# VNH5019.net
KiCad netlist of a schematic drawn in Altium Designer
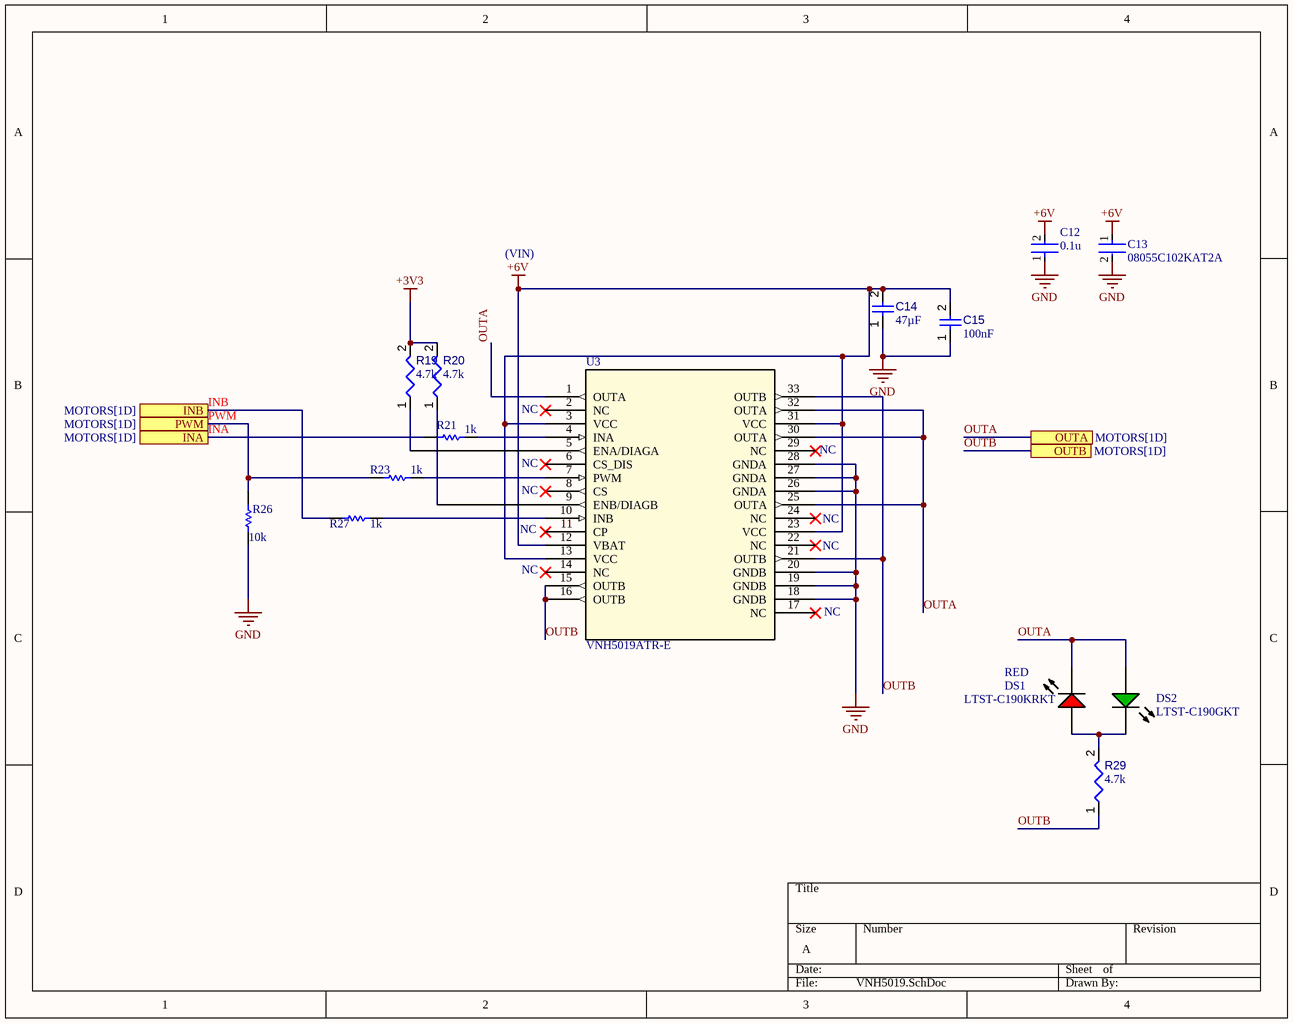
[diagram p0: VNH5019.SchDoc]

(export (version "E")
  (design (tool "Eeschema 10.0.6"))
  (components
    (comp (ref "C12")
      (value "0.1u")
      (footprint "FP-CL21-IPC_A")
      (description "CL21 Series 0805 100nF 100V ±10% Tolerance X7R Multilayer Ceramic Chip Capacitor")
      (libsource (lib "Altium Content Vault") (part "b4654b650e69147ec39a6b967a45e02"))
    )
    (comp (ref "C13")
      (value "08055C102KAT2A")
      (footprint "FP-0805-L_2_01_0_2-W_1_25-IPC_C")
      (description "General Purpose Ceramic Capacitor, 0805, 1nF, 10%, X7R, 0.15, 50V")
      (fields (field (name "VOLTAGE") "50V") (field (name "TOLERANCE") "10%"))
      (libsource (lib "Altium Content Vault") (part "02cd4be3c70576c341d710602a673aa"))
    )
    (comp (ref "C14")
      (value "47µF")
      (footprint "CAPC0805(2012)145_L")
      (description "Chip Capacitor, 47µF +/-40%, 6.3V, 0805, Thickness 1.45 mm")
      (fields (field (name "TOLERANCE") "10%") (field (name "Comment") "Capacitor 47µF +/-40% 6.3V 0805"))
      (libsource (lib "Northeastern University - Generate") (part "CAP-NP-2"))
    )
    (comp (ref "C15")
      (value "100nF")
      (footprint "CAPC2013X95X50LL10T25")
      (description "Chip Capacitor, 100 nF, +/- 10%, 50 V, 0805 (2012 Metric)")
      (fields (field (name "TOLERANCE") "10%") (field (name "Comment") "Capacitor 100 nF +/-10% 50 V 0805"))
      (libsource (lib "Northeastern University - Generate") (part "CAP-NP-2"))
    )
    (comp (ref "DS1")
      (value "LTST-C190KRKT")
      (footprint "LTST-C191KRKT_V")
      (description "LED Uni-Color Red, 62.5 mW, 25 mA, -30 to 85 degC, 2-Pin SMD, RoHS, Tape and Reel")
      (fields (field (name "POWER") "75mW") (field (name "MANUFACTURER") "Lite-On"))
      (libsource (lib "Northeastern University - Generate") (part "LED-RED-AK-2"))
    )
    (comp (ref "DS2")
      (value "LTST-C190GKT")
      (footprint "LTST-C190GKT_V")
      (description "LED Uni-Color Green, 100 mW, 30 mA, -55 to 85 degC, 2-Pin SMD, RoHS, Tape and Reel")
      (fields (field (name "POWER") "100mW") (field (name "MANUFACTURER") "Lite-On"))
      (libsource (lib "Northeastern University - Generate") (part "LED-GREEN-AK-2"))
    )
    (comp (ref "R19")
      (value "4.7k")
      (footprint "RESC2013X70X40ML20T20")
      (description "Chip Resistor, 4.7 KOhm, +/- 1%, 0.125 W, -55 to 155 degC, 0805 (2012 Metric)")
      (fields (field (name "POWER") "125mW") (field (name "TOLERANCE") "1%"))
      (libsource (lib "Northeastern University - Generate") (part "RES-2"))
    )
    (comp (ref "R20")
      (value "4.7k")
      (footprint "RESC2013X70X40ML20T20")
      (description "Chip Resistor, 4.7 KOhm, +/- 1%, 0.125 W, -55 to 155 degC, 0805 (2012 Metric)")
      (fields (field (name "POWER") "125mW") (field (name "TOLERANCE") "1%"))
      (libsource (lib "Northeastern University - Generate") (part "RES-2"))
    )
    (comp (ref "R21")
      (value "1k")
      (footprint "RESC2013X60X35ML10T20")
      (description "Chip Resistor, 1 KOhm, +/- 1%, 125 mW, -55 to 155 degC, 0805 (2012 Metric), RoHS, Tape and Reel")
      (fields (field (name "TOLERANCE") "1%") (field (name "MANUFACTURER") "Yageo"))
      (libsource (lib "Altium Content Vault") (part "RES-2"))
    )
    (comp (ref "R23")
      (value "1k")
      (footprint "RESC2013X60X35ML10T20")
      (description "Chip Resistor, 1 KOhm, +/- 1%, 125 mW, -55 to 155 degC, 0805 (2012 Metric), RoHS, Tape and Reel")
      (fields (field (name "TOLERANCE") "1%") (field (name "MANUFACTURER") "Yageo"))
      (libsource (lib "Altium Content Vault") (part "RES-2"))
    )
    (comp (ref "R26")
      (value "10k")
      (footprint "RESC2013X60X40LL20T25_A")
      (fields (field (name "TOLERANCE") "0.1%") (field (name "MANUFACTURER") "Panasonic"))
      (libsource (lib "Altium Content Vault") (part "RES-2"))
    )
    (comp (ref "R27")
      (value "1k")
      (footprint "RESC2013X60X35ML10T20")
      (description "Chip Resistor, 1 KOhm, +/- 1%, 125 mW, -55 to 155 degC, 0805 (2012 Metric), RoHS, Tape and Reel")
      (fields (field (name "TOLERANCE") "1%") (field (name "MANUFACTURER") "Yageo"))
      (libsource (lib "Altium Content Vault") (part "RES-2"))
    )
    (comp (ref "R29")
      (value "4.7k")
      (footprint "RESC2013X70X40ML20T20")
      (description "Chip Resistor, 4.7 KOhm, +/- 1%, 0.125 W, -55 to 155 degC, 0805 (2012 Metric)")
      (fields (field (name "POWER") "125mW") (field (name "TOLERANCE") "1%"))
      (libsource (lib "Northeastern University - Generate") (part "RES-2"))
    )
    (comp (ref "U3")
      (value "VNH5019ATR-E")
      (footprint "MultiPowerSO-30_STM")
      (description "No Description Available")
      (libsource (lib "Northeastern University - Generate") (part "VNH5019ATR-E"))
    )
  )
  (nets
    (net (code "1") (name "+3V3") (class "Default")
      (node (ref "R19") (pin "2") (pinfunction "2_2") (pintype "passive"))
      (node (ref "R20") (pin "2") (pinfunction "2_2") (pintype "passive"))
    )
    (net (code "2") (name "+6V") (class "Default")
      (node (ref "C12") (pin "2") (pinfunction "2_2") (pintype "passive"))
      (node (ref "C13") (pin "1") (pinfunction "1_1") (pintype "passive"))
      (node (ref "C14") (pin "2") (pinfunction "2_2") (pintype "passive"))
      (node (ref "C15") (pin "2") (pinfunction "2_2") (pintype "passive"))
      (node (ref "U3") (pin "12") (pinfunction "VBAT_12") (pintype "power_in"))
      (node (ref "U3") (pin "13") (pinfunction "VCC_13") (pintype "power_in"))
      (node (ref "U3") (pin "23") (pinfunction "VCC_23") (pintype "power_in"))
      (node (ref "U3") (pin "3") (pinfunction "VCC_3") (pintype "power_in"))
      (node (ref "U3") (pin "31") (pinfunction "VCC_31") (pintype "power_in"))
    )
    (net (code "3") (name "/INA") (class "Default")
      (node (ref "R21") (pin "2") (pinfunction "2_2") (pintype "passive"))
    )
    (net (code "4") (name "/INB") (class "Default")
      (node (ref "R27") (pin "2") (pinfunction "2_2") (pintype "passive"))
    )
    (net (code "5") (name "/OUTA") (class "Default")
      (node (ref "DS1") (pin "2") (pinfunction "K_2") (pintype "passive"))
      (node (ref "DS2") (pin "1") (pinfunction "A_1") (pintype "passive"))
      (node (ref "U3") (pin "1") (pinfunction "OUTA_1") (pintype "output"))
      (node (ref "U3") (pin "25") (pinfunction "OUTA_25") (pintype "output"))
      (node (ref "U3") (pin "30") (pinfunction "OUTA_30") (pintype "output"))
      (node (ref "U3") (pin "32") (pinfunction "OUTA_32") (pintype "output"))
    )
    (net (code "6") (name "/OUTB") (class "Default")
      (node (ref "R29") (pin "1") (pinfunction "1_1") (pintype "passive"))
      (node (ref "U3") (pin "15") (pinfunction "OUTB_15") (pintype "output"))
      (node (ref "U3") (pin "16") (pinfunction "OUTB_16") (pintype "output"))
      (node (ref "U3") (pin "21") (pinfunction "OUTB_21") (pintype "output"))
      (node (ref "U3") (pin "33") (pinfunction "OUTB_33") (pintype "output"))
    )
    (net (code "7") (name "/PWM") (class "Default")
      (node (ref "R23") (pin "2") (pinfunction "2_2") (pintype "passive"))
      (node (ref "R26") (pin "2") (pinfunction "2_2") (pintype "passive"))
    )
    (net (code "8") (name "GND") (class "Default")
      (node (ref "C12") (pin "1") (pinfunction "1_1") (pintype "passive"))
      (node (ref "C13") (pin "2") (pinfunction "2_2") (pintype "passive"))
      (node (ref "C14") (pin "1") (pinfunction "1_1") (pintype "passive"))
      (node (ref "C15") (pin "1") (pinfunction "1_1") (pintype "passive"))
      (node (ref "R26") (pin "1") (pinfunction "1_1") (pintype "passive"))
      (node (ref "U3") (pin "18") (pinfunction "GNDB_18") (pintype "power_in"))
      (node (ref "U3") (pin "19") (pinfunction "GNDB_19") (pintype "power_in"))
      (node (ref "U3") (pin "20") (pinfunction "GNDB_20") (pintype "power_in"))
      (node (ref "U3") (pin "26") (pinfunction "GNDA_26") (pintype "power_in"))
      (node (ref "U3") (pin "27") (pinfunction "GNDA_27") (pintype "power_in"))
      (node (ref "U3") (pin "28") (pinfunction "GNDA_28") (pintype "power_in"))
    )
    (net (code "9") (name "Net-(DS1-A)") (class "Default")
      (node (ref "DS1") (pin "1") (pinfunction "A_1") (pintype "passive"))
      (node (ref "DS2") (pin "2") (pinfunction "K_2") (pintype "passive"))
      (node (ref "R29") (pin "2") (pinfunction "2_2") (pintype "passive"))
    )
    (net (code "10") (name "Net-(U3-ENA{slash}DIAGA)") (class "Default")
      (node (ref "R19") (pin "1") (pinfunction "1_1") (pintype "passive"))
      (node (ref "U3") (pin "5") (pinfunction "ENA/DIAGA_5") (pintype "output"))
    )
    (net (code "11") (name "Net-(U3-ENB{slash}DIAGB)") (class "Default")
      (node (ref "R20") (pin "1") (pinfunction "1_1") (pintype "passive"))
      (node (ref "U3") (pin "9") (pinfunction "ENB/DIAGB_9") (pintype "output"))
    )
    (net (code "12") (name "Net-(U3-INA)") (class "Default")
      (node (ref "R21") (pin "1") (pinfunction "1_1") (pintype "passive"))
      (node (ref "U3") (pin "4") (pinfunction "INA_4") (pintype "input"))
    )
    (net (code "13") (name "Net-(U3-INB)") (class "Default")
      (node (ref "R27") (pin "1") (pinfunction "1_1") (pintype "passive"))
      (node (ref "U3") (pin "10") (pinfunction "INB_10") (pintype "input"))
    )
    (net (code "14") (name "Net-(U3-PWM)") (class "Default")
      (node (ref "R23") (pin "1") (pinfunction "1_1") (pintype "passive"))
      (node (ref "U3") (pin "7") (pinfunction "PWM_7") (pintype "input"))
    )
    (net (code "15") (name "unconnected-(U3-CP-Pad11)") (class "Default")
      (node (ref "U3") (pin "11") (pinfunction "CP_11") (pintype "passive+no_connect"))
    )
    (net (code "16") (name "unconnected-(U3-CS-Pad8)") (class "Default")
      (node (ref "U3") (pin "8") (pinfunction "CS_8") (pintype "output+no_connect"))
    )
    (net (code "17") (name "unconnected-(U3-CS_DIS-Pad6)") (class "Default")
      (node (ref "U3") (pin "6") (pinfunction "CS_DIS_6") (pintype "passive+no_connect"))
    )
    (net (code "18") (name "unconnected-(U3-NC-Pad2)") (class "Default")
      (node (ref "U3") (pin "2") (pinfunction "NC_2") (pintype "passive+no_connect"))
    )
    (net (code "19") (name "unconnected-(U3-NC-Pad14)") (class "Default")
      (node (ref "U3") (pin "14") (pinfunction "NC_14") (pintype "passive+no_connect"))
    )
    (net (code "20") (name "unconnected-(U3-NC-Pad17)") (class "Default")
      (node (ref "U3") (pin "17") (pinfunction "NC_17") (pintype "passive+no_connect"))
    )
    (net (code "21") (name "unconnected-(U3-NC-Pad22)") (class "Default")
      (node (ref "U3") (pin "22") (pinfunction "NC_22") (pintype "passive+no_connect"))
    )
    (net (code "22") (name "unconnected-(U3-NC-Pad24)") (class "Default")
      (node (ref "U3") (pin "24") (pinfunction "NC_24") (pintype "passive+no_connect"))
    )
    (net (code "23") (name "unconnected-(U3-NC-Pad29)") (class "Default")
      (node (ref "U3") (pin "29") (pinfunction "NC_29") (pintype "passive+no_connect"))
    )
  )
)
